# ADCs.net
KiCad netlist of a schematic drawn in Altium Designer
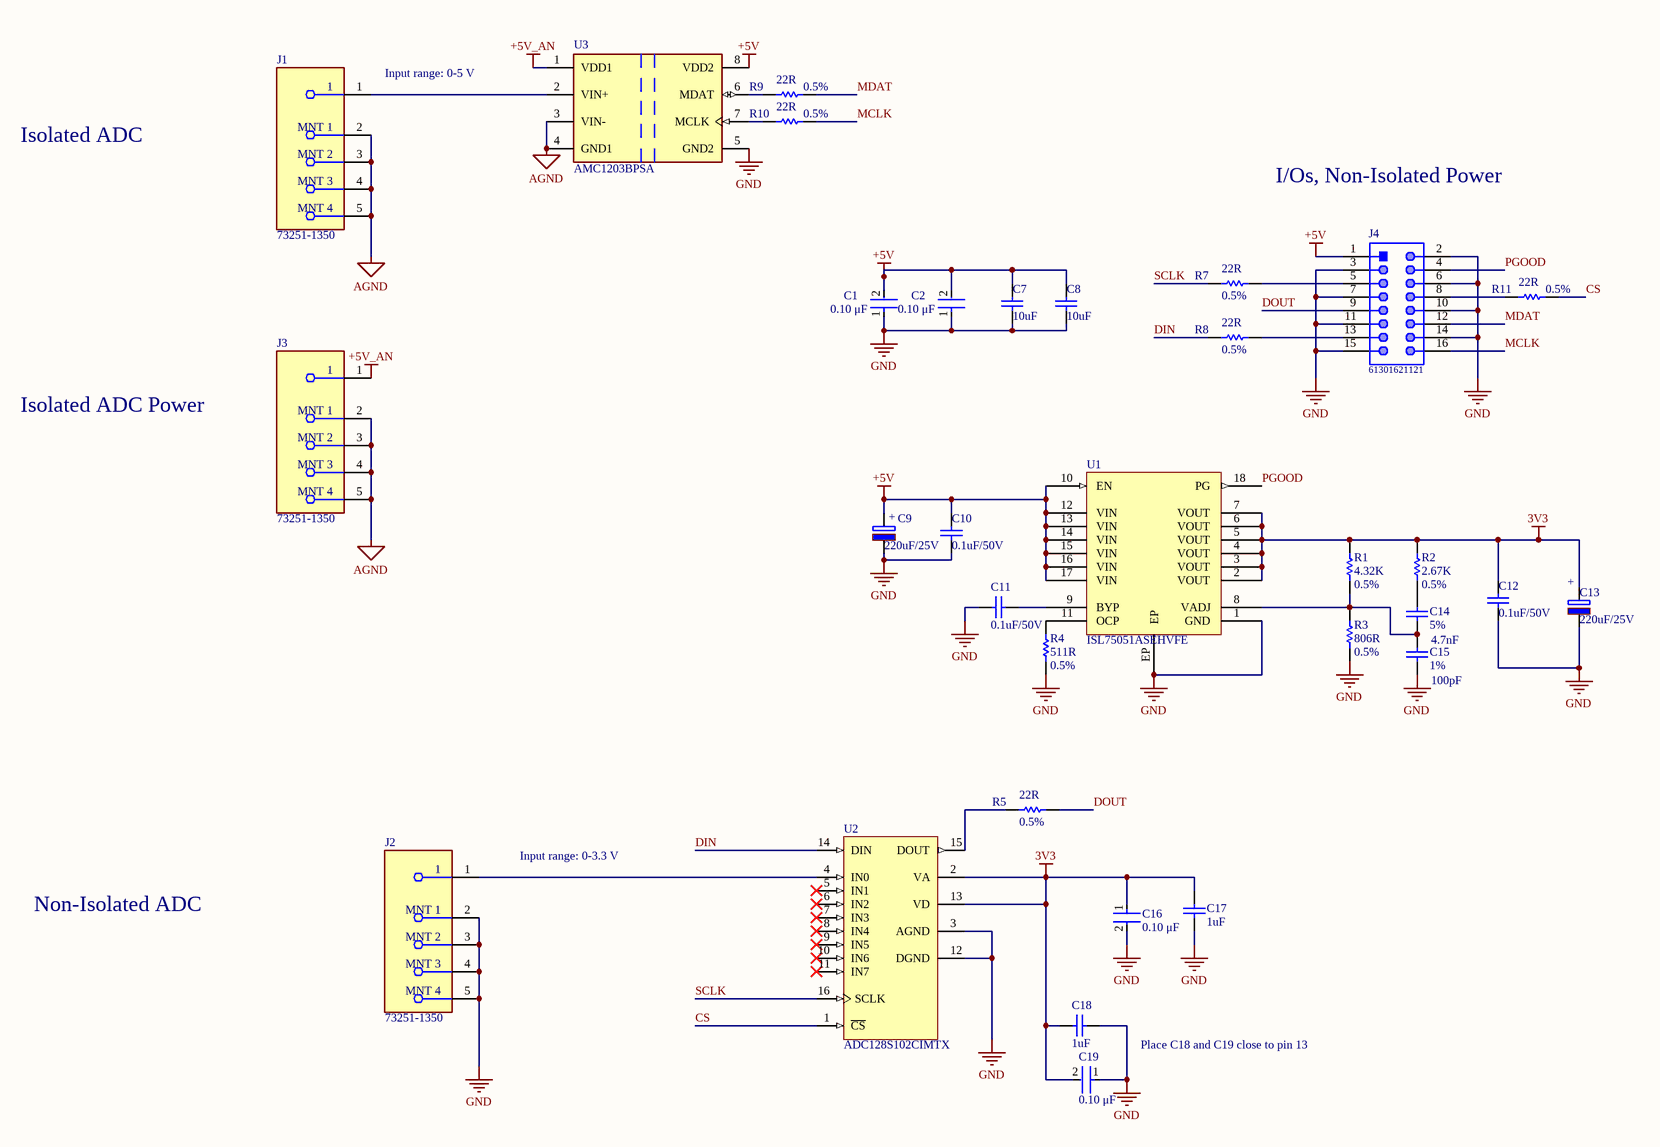
[diagram p0: ADCs.SchDoc]

(export (version "E")
  (design (tool "Eeschema 10.0.6"))
  (components
    (comp (ref "C1")
      (value "0.10 μF")
      (footprint "FP-C0603C-CF-MFG")
      (description "CAP CER 0.1UF 50V 5% X7R 0603")
      (fields (field (name "TOLERANCE") "0.05") (field (name "MANUFACTURER PART NUMBER") "C0603C104J5RACTU"))
      (libsource (lib "Altium Content Vault") (part "b4654b650e69147ec39a6b967a45e02"))
    )
    (comp (ref "C2")
      (value "0.10 μF")
      (footprint "FP-C0603C-CF-MFG")
      (description "CAP CER 0.1UF 50V 5% X7R 0603")
      (fields (field (name "TOLERANCE") "0.05") (field (name "MANUFACTURER PART NUMBER") "C0603C104J5RACTU"))
      (libsource (lib "Altium Content Vault") (part "b4654b650e69147ec39a6b967a45e02"))
    )
    (comp (ref "C7")
      (value "10uF")
      (footprint "CAPC1608X90N")
      (description "CAP CER 10UF 25V X5R 0603")
      (fields
        (field (name "MANUFACTURER PART NUMBER") "GRM188R61E106KA73D")
        (field (name "MANUFACTURER") "Murata Electronics")
      )
      (libsource (lib "Motor Resolver") (part "CAP CER 10UF 25V X5R 0603"))
    )
    (comp (ref "C8")
      (value "10uF")
      (footprint "CAPC1608X90N")
      (description "CAP CER 10UF 25V X5R 0603")
      (fields
        (field (name "MANUFACTURER PART NUMBER") "GRM188R61E106KA73D")
        (field (name "MANUFACTURER") "Murata Electronics")
      )
      (libsource (lib "Motor Resolver") (part "CAP CER 10UF 25V X5R 0603"))
    )
    (comp (ref "C9")
      (value "220uF/25V")
      (footprint "CAP_AE830X1050N")
      (description "CAP ALUM 220UF 20% 25V SMD")
      (fields
        (field (name "MANUFACTURER PART NUMBER") "EMZA250ADA221MHA0G")
        (field (name "MANUFACTURER") "United Chemi-Con")
      )
      (libsource (lib "") (part "CAP ALUM 220UF 20% 25V SMD_1"))
    )
    (comp (ref "C10")
      (value "0.1uF/50V")
      (footprint "CAPC1608X90N")
      (description "CAP CER 0.1UF 50V X7R 0603")
      (fields
        (field (name "MANUFACTURER PART NUMBER") "CL10B104KB8NNNC")
        (field (name "MANUFACTURER") "Samsung Electro-Mechanics")
      )
      (libsource (lib "Motor Resolver") (part "CAP CER 0.1UF 50V X7R 0603"))
    )
    (comp (ref "C11")
      (value "0.1uF/50V")
      (footprint "CAPC1608X90N")
      (description "CAP CER 0.1UF 50V X7R 0603")
      (fields
        (field (name "MANUFACTURER PART NUMBER") "CL10B104KB8NNNC")
        (field (name "MANUFACTURER") "Samsung Electro-Mechanics")
      )
      (libsource (lib "Motor Resolver") (part "CAP CER 0.1UF 50V X7R 0603"))
    )
    (comp (ref "C12")
      (value "0.1uF/50V")
      (footprint "CAPC1608X90N")
      (description "CAP CER 0.1UF 50V X7R 0603")
      (fields
        (field (name "MANUFACTURER PART NUMBER") "CL10B104KB8NNNC")
        (field (name "MANUFACTURER") "Samsung Electro-Mechanics")
      )
      (libsource (lib "Motor Resolver") (part "CAP CER 0.1UF 50V X7R 0603"))
    )
    (comp (ref "C13")
      (value "220uF/25V")
      (footprint "CAP_AE830X1050N")
      (description "CAP ALUM 220UF 20% 25V SMD")
      (fields
        (field (name "MANUFACTURER PART NUMBER") "EMZA250ADA221MHA0G")
        (field (name "MANUFACTURER") "United Chemi-Con")
      )
      (libsource (lib "Motor Resolver") (part "CAP ALUM 220UF 20% 25V SMD"))
    )
    (comp (ref "C14")
      (value "4.7nF")
      (footprint "CAPC1608X90N")
      (description "CAP CER 4700PF 50V C0G 0603")
      (fields
        (field (name "MANUFACTURER PART NUMBER") "CGA3E2C0G1H472J080AA")
        (field (name "MANUFACTURER") "TDK Corporation")
        (field (name "TOLERANCE") "5%")
      )
      (libsource (lib "Motor Resolver") (part "CAP CER 4700PF 50V C0G 0603"))
    )
    (comp (ref "C15")
      (value "100pF")
      (footprint "CAPC1608X90N")
      (description "CAP CER 100PF 50V C0G/NP0 0603")
      (fields
        (field (name "MANUFACTURER PART NUMBER") "06035A101FAT2A")
        (field (name "MANUFACTURER") "KYOCERA AVX")
        (field (name "TOLERANCE") "1%")
      )
      (libsource (lib "Motor Resolver") (part "CAP CER 100PF 50V C0G/NP0 0603"))
    )
    (comp (ref "C16")
      (value "0.10 μF")
      (footprint "FP-C0603C-CF-MFG")
      (description "CAP CER 0.1UF 50V 5% X7R 0603")
      (fields (field (name "TOLERANCE") "0.05") (field (name "MANUFACTURER PART NUMBER") "C0603C104J5RACTU"))
      (libsource (lib "Altium Content Vault") (part "b4654b650e69147ec39a6b967a45e02"))
    )
    (comp (ref "C17")
      (value "1uF")
      (footprint "CAPC1608X90N")
      (description "CAP CER 1UF 25V X7R 0603")
      (fields
        (field (name "MANUFACTURER PART NUMBER") "GCM188R71E105KA64D")
        (field (name "MANUFACTURER") "Murata Electronics")
      )
      (libsource (lib "Motor Resolver") (part "CAP CER 1UF 25V X7R 0603"))
    )
    (comp (ref "C18")
      (value "1uF")
      (footprint "CAPC1608X90N")
      (description "CAP CER 1UF 25V X7R 0603")
      (fields
        (field (name "MANUFACTURER PART NUMBER") "GCM188R71E105KA64D")
        (field (name "MANUFACTURER") "Murata Electronics")
      )
      (libsource (lib "Motor Resolver") (part "CAP CER 1UF 25V X7R 0603"))
    )
    (comp (ref "C19")
      (value "0.10 μF")
      (footprint "FP-C0603C-CF-MFG")
      (description "CAP CER 0.1UF 50V 5% X7R 0603")
      (fields (field (name "TOLERANCE") "0.05") (field (name "MANUFACTURER PART NUMBER") "C0603C104J5RACTU"))
      (libsource (lib "Altium Content Vault") (part "b4654b650e69147ec39a6b967a45e02"))
    )
    (comp (ref "J1")
      (value "73251-1350")
      (footprint "FP-73251-1350-MFG")
      (description "CONN SMA JACK STR 50 OHM SMD")
      (fields
        (field (name "OCTOPART") "https://octopart.com/73251-1350-molex-5414390")
        (field (name "MANUFACTURER") "Molex")
      )
      (libsource (lib "Altium Content Vault") (part "474d33b8a96b1ade9ed6dd87a2b06d4"))
    )
    (comp (ref "J2")
      (value "73251-1350")
      (footprint "FP-73251-1350-MFG")
      (description "CONN SMA JACK STR 50 OHM SMD")
      (fields
        (field (name "OCTOPART") "https://octopart.com/73251-1350-molex-5414390")
        (field (name "MANUFACTURER") "Molex")
      )
      (libsource (lib "Altium Content Vault") (part "474d33b8a96b1ade9ed6dd87a2b06d4"))
    )
    (comp (ref "J3")
      (value "73251-1350")
      (footprint "FP-73251-1350-MFG")
      (description "CONN SMA JACK STR 50 OHM SMD")
      (fields
        (field (name "OCTOPART") "https://octopart.com/73251-1350-molex-5414390")
        (field (name "MANUFACTURER") "Molex")
      )
      (libsource (lib "Altium Content Vault") (part "474d33b8a96b1ade9ed6dd87a2b06d4"))
    )
    (comp (ref "J4")
      (value "61301621121")
      (footprint "61301621121")
      (description "THT Vertical Pin Header WR-PHD, Pitch 2.54 mm, Dual Row, 16 pins")
      (fields (field (name "MANUFACTURER") "Wurth Elektronik") (field (name "PUBLISHER") "WurthElektronik"))
      (libsource (lib "Altium Content Vault") (part "WE-CN-2P-M-R16"))
    )
    (comp (ref "R1")
      (value "4.32K")
      (footprint "RESC1608X55N")
      (description "RES SMD 4.32K OHM 0.5% 1/5W 0603")
      (fields
        (field (name "MANUFACTURER") "Panasonic Electronic Components")
        (field (name "MANUFACTURER PART NUMBER") "ERJ-PB3D4321V")
        (field (name "TOLERANCE") "0.5%")
      )
      (libsource (lib "Motor Resolver") (part "RES SMD 4.32K OHM 0.5% 1/5W 0603"))
    )
    (comp (ref "R2")
      (value "2.67K")
      (footprint "RESC1608X55N")
      (description "RES SMD 2.67KOHM 0.5% 1/10W 0603")
      (fields
        (field (name "MANUFACTURER") "Yageo")
        (field (name "MANUFACTURER PART NUMBER") "RT0603DRD072K67L")
        (field (name "TOLERANCE") "0.5%")
      )
      (libsource (lib "Motor Resolver") (part "RES SMD 2.67KOHM 0.5% 1/10W 0603"))
    )
    (comp (ref "R3")
      (value "806R")
      (footprint "RESC1608X55N")
      (description "RES SMD 806 OHM 0.5% 1/10W 0603")
      (fields
        (field (name "MANUFACTURER") "Yageo")
        (field (name "MANUFACTURER PART NUMBER") "RT0603DRD0762KL")
        (field (name "TOLERANCE") "0.5%")
      )
      (libsource (lib "Motor Resolver") (part "RES SMD 806 OHM 0.5% 1/10W 0603"))
    )
    (comp (ref "R4")
      (value "511R")
      (footprint "RESC1608X55N")
      (description "RES SMD 511 OHM 1% 1/10W 0603")
      (fields
        (field (name "MANUFACTURER") "Panasonic Electronic Components")
        (field (name "MANUFACTURER PART NUMBER") "ERJ-3EKF5110V")
        (field (name "TOLERANCE") "0.5%")
      )
      (libsource (lib "Motor Resolver") (part "RES SMD 511 OHM 1% 1/10W 0603"))
    )
    (comp (ref "R5")
      (value "22R")
      (footprint "RESC1608X55N")
      (description "RES SMD 22 OHM 0.5% 1/10W 0603")
      (fields
        (field (name "MANUFACTURER") "Yageo")
        (field (name "MANUFACTURER PART NUMBER") "RT0603DRD0722RL")
        (field (name "TOLERANCE") "0.5%")
      )
      (libsource (lib "Motor Resolver") (part "RES SMD 22 OHM 0.5% 1/10W 0603"))
    )
    (comp (ref "R7")
      (value "22R")
      (footprint "RESC1608X55N")
      (description "RES SMD 22 OHM 0.5% 1/10W 0603")
      (fields
        (field (name "MANUFACTURER") "Yageo")
        (field (name "MANUFACTURER PART NUMBER") "RT0603DRD0722RL")
        (field (name "TOLERANCE") "0.5%")
      )
      (libsource (lib "Motor Resolver") (part "RES SMD 22 OHM 0.5% 1/10W 0603"))
    )
    (comp (ref "R8")
      (value "22R")
      (footprint "RESC1608X55N")
      (description "RES SMD 22 OHM 0.5% 1/10W 0603")
      (fields
        (field (name "MANUFACTURER") "Yageo")
        (field (name "MANUFACTURER PART NUMBER") "RT0603DRD0722RL")
        (field (name "TOLERANCE") "0.5%")
      )
      (libsource (lib "Motor Resolver") (part "RES SMD 22 OHM 0.5% 1/10W 0603"))
    )
    (comp (ref "R9")
      (value "22R")
      (footprint "RESC1608X55N")
      (description "RES SMD 22 OHM 0.5% 1/10W 0603")
      (fields
        (field (name "MANUFACTURER") "Yageo")
        (field (name "MANUFACTURER PART NUMBER") "RT0603DRD0722RL")
        (field (name "TOLERANCE") "0.5%")
      )
      (libsource (lib "Motor Resolver") (part "RES SMD 22 OHM 0.5% 1/10W 0603"))
    )
    (comp (ref "R10")
      (value "22R")
      (footprint "RESC1608X55N")
      (description "RES SMD 22 OHM 0.5% 1/10W 0603")
      (fields
        (field (name "MANUFACTURER") "Yageo")
        (field (name "MANUFACTURER PART NUMBER") "RT0603DRD0722RL")
        (field (name "TOLERANCE") "0.5%")
      )
      (libsource (lib "Motor Resolver") (part "RES SMD 22 OHM 0.5% 1/10W 0603"))
    )
    (comp (ref "R11")
      (value "22R")
      (footprint "RESC1608X55N")
      (description "RES SMD 22 OHM 0.5% 1/10W 0603")
      (fields
        (field (name "MANUFACTURER") "Yageo")
        (field (name "MANUFACTURER PART NUMBER") "RT0603DRD0722RL")
        (field (name "TOLERANCE") "0.5%")
      )
      (libsource (lib "Motor Resolver") (part "RES SMD 22 OHM 0.5% 1/10W 0603"))
    )
    (comp (ref "U1")
      (value "ISL75051ASEHVFE")
      (footprint "CFP102P1520X310-18AN")
      (description "Voltage regulator, linear, variable, 3 A, CFP-18 exposed pad, class V")
      (fields
        (field (name "MANUFACTURER") "Renesas / Intersil")
        (field (name "FM (SMD) PART NUMBER") "5962R1121203VYC")
      )
      (libsource (lib "Motor Resolver") (part "ISL75051ASEHVFE"))
    )
    (comp (ref "U2")
      (value "ADC128S102CIMTX")
      (footprint "MTC16_N")
      (description "8-Channel, 500 kSPS to 1 MSPS, 12-Bit A/D Converter, 16-pin TSSOP")
      (fields (field (name "MANUFACTURER") "National Semiconductor"))
      (libsource (lib "Altium Content Vault") (part "CON-ADC-ADC108S052CIMT"))
    )
    (comp (ref "U3")
      (value "AMC1203BPSA")
      (footprint "FP-PSA0008A-IPC_C")
      (description "IC ADC 16BIT SIGMA-DELTA 8SOP")
      (libsource (lib "Altium Content Vault") (part "402472702e68974f8122a6dcee3cdea"))
    )
  )
  (nets
    (net (code "1") (name "+5V") (class "Default")
      (node (ref "C1") (pin "2") (pinfunction "2_2") (pintype "passive"))
      (node (ref "C10") (pin "1") (pinfunction "1_1") (pintype "passive"))
      (node (ref "C2") (pin "2") (pinfunction "2_2") (pintype "passive"))
      (node (ref "C7") (pin "1") (pinfunction "1_1") (pintype "passive"))
      (node (ref "C8") (pin "1") (pinfunction "1_1") (pintype "passive"))
      (node (ref "C9") (pin "1") (pinfunction "1_1") (pintype "passive"))
      (node (ref "J4") (pin "1") (pinfunction "1_1") (pintype "passive"))
      (node (ref "U1") (pin "10") (pinfunction "EN_10") (pintype "input"))
      (node (ref "U1") (pin "12") (pinfunction "VIN_12") (pintype "power_in"))
      (node (ref "U1") (pin "13") (pinfunction "VIN_13") (pintype "power_in"))
      (node (ref "U1") (pin "14") (pinfunction "VIN_14") (pintype "power_in"))
      (node (ref "U1") (pin "15") (pinfunction "VIN_15") (pintype "power_in"))
      (node (ref "U1") (pin "16") (pinfunction "VIN_16") (pintype "power_in"))
      (node (ref "U1") (pin "17") (pinfunction "VIN_17") (pintype "power_in"))
      (node (ref "U3") (pin "8") (pinfunction "VDD2_8") (pintype "power_in"))
    )
    (net (code "2") (name "+5V_AN") (class "Default")
      (node (ref "J3") (pin "1") (pinfunction "1_1") (pintype "passive"))
      (node (ref "U3") (pin "1") (pinfunction "VDD1_1") (pintype "power_in"))
    )
    (net (code "3") (name "/CS") (class "Default")
      (node (ref "R11") (pin "2") (pinfunction "2_2") (pintype "passive"))
      (node (ref "U2") (pin "1") (pinfunction "~{CS}_1") (pintype "input"))
    )
    (net (code "4") (name "/DIN") (class "Default")
      (node (ref "R8") (pin "1") (pinfunction "1_1") (pintype "passive"))
      (node (ref "U2") (pin "14") (pinfunction "DIN_14") (pintype "input"))
    )
    (net (code "5") (name "/DOUT") (class "Default")
      (node (ref "J4") (pin "9") (pinfunction "9_9") (pintype "passive"))
      (node (ref "R5") (pin "2") (pinfunction "2_2") (pintype "passive"))
    )
    (net (code "6") (name "/MCLK") (class "Default")
      (node (ref "J4") (pin "16") (pinfunction "16_16") (pintype "passive"))
      (node (ref "R10") (pin "2") (pinfunction "2_2") (pintype "passive"))
    )
    (net (code "7") (name "/MDAT") (class "Default")
      (node (ref "J4") (pin "12") (pinfunction "12_12") (pintype "passive"))
      (node (ref "R9") (pin "2") (pinfunction "2_2") (pintype "passive"))
    )
    (net (code "8") (name "/PGOOD") (class "Default")
      (node (ref "J4") (pin "4") (pinfunction "4_4") (pintype "passive"))
      (node (ref "U1") (pin "18") (pinfunction "PG_18") (pintype "output"))
    )
    (net (code "9") (name "/SCLK") (class "Default")
      (node (ref "R7") (pin "1") (pinfunction "1_1") (pintype "passive"))
      (node (ref "U2") (pin "16") (pinfunction "SCLK_16") (pintype "input"))
    )
    (net (code "10") (name "3V3") (class "Default")
      (node (ref "C12") (pin "1") (pinfunction "1_1") (pintype "passive"))
      (node (ref "C13") (pin "1") (pinfunction "1_1") (pintype "passive"))
      (node (ref "C16") (pin "1") (pinfunction "1_1") (pintype "passive"))
      (node (ref "C17") (pin "1") (pinfunction "1_1") (pintype "passive"))
      (node (ref "C18") (pin "2") (pinfunction "2_2") (pintype "passive"))
      (node (ref "C19") (pin "2") (pinfunction "2_2") (pintype "passive"))
      (node (ref "R1") (pin "2") (pinfunction "2_2") (pintype "passive"))
      (node (ref "R2") (pin "2") (pinfunction "2_2") (pintype "passive"))
      (node (ref "U1") (pin "2") (pinfunction "VOUT_2") (pintype "power_in"))
      (node (ref "U1") (pin "3") (pinfunction "VOUT_3") (pintype "power_in"))
      (node (ref "U1") (pin "4") (pinfunction "VOUT_4") (pintype "power_in"))
      (node (ref "U1") (pin "5") (pinfunction "VOUT_5") (pintype "power_in"))
      (node (ref "U1") (pin "6") (pinfunction "VOUT_6") (pintype "power_in"))
      (node (ref "U1") (pin "7") (pinfunction "VOUT_7") (pintype "power_in"))
      (node (ref "U2") (pin "13") (pinfunction "VD_13") (pintype "power_in"))
      (node (ref "U2") (pin "2") (pinfunction "VA_2") (pintype "power_in"))
    )
    (net (code "11") (name "AGND") (class "Default")
      (node (ref "J1") (pin "2") (pinfunction "MNT_1_2") (pintype "passive"))
      (node (ref "J1") (pin "3") (pinfunction "MNT_2_3") (pintype "passive"))
      (node (ref "J1") (pin "4") (pinfunction "MNT_3_4") (pintype "passive"))
      (node (ref "J1") (pin "5") (pinfunction "MNT_4_5") (pintype "passive"))
      (node (ref "J3") (pin "2") (pinfunction "MNT_1_2") (pintype "passive"))
      (node (ref "J3") (pin "3") (pinfunction "MNT_2_3") (pintype "passive"))
      (node (ref "J3") (pin "4") (pinfunction "MNT_3_4") (pintype "passive"))
      (node (ref "J3") (pin "5") (pinfunction "MNT_4_5") (pintype "passive"))
      (node (ref "U3") (pin "3") (pinfunction "VIN-_3") (pintype "tri_state"))
      (node (ref "U3") (pin "4") (pinfunction "GND1_4") (pintype "power_in"))
    )
    (net (code "12") (name "GND") (class "Default")
      (node (ref "C1") (pin "1") (pinfunction "1_1") (pintype "passive"))
      (node (ref "C10") (pin "2") (pinfunction "2_2") (pintype "passive"))
      (node (ref "C11") (pin "2") (pinfunction "2_2") (pintype "passive"))
      (node (ref "C12") (pin "2") (pinfunction "2_2") (pintype "passive"))
      (node (ref "C13") (pin "2") (pinfunction "2_2") (pintype "passive"))
      (node (ref "C15") (pin "2") (pinfunction "2_2") (pintype "passive"))
      (node (ref "C16") (pin "2") (pinfunction "2_2") (pintype "passive"))
      (node (ref "C17") (pin "2") (pinfunction "2_2") (pintype "passive"))
      (node (ref "C18") (pin "1") (pinfunction "1_1") (pintype "passive"))
      (node (ref "C19") (pin "1") (pinfunction "1_1") (pintype "passive"))
      (node (ref "C2") (pin "1") (pinfunction "1_1") (pintype "passive"))
      (node (ref "C7") (pin "2") (pinfunction "2_2") (pintype "passive"))
      (node (ref "C8") (pin "2") (pinfunction "2_2") (pintype "passive"))
      (node (ref "C9") (pin "2") (pinfunction "2_2") (pintype "passive"))
      (node (ref "J2") (pin "2") (pinfunction "MNT_1_2") (pintype "passive"))
      (node (ref "J2") (pin "3") (pinfunction "MNT_2_3") (pintype "passive"))
      (node (ref "J2") (pin "4") (pinfunction "MNT_3_4") (pintype "passive"))
      (node (ref "J2") (pin "5") (pinfunction "MNT_4_5") (pintype "passive"))
      (node (ref "J4") (pin "10") (pinfunction "10_10") (pintype "passive"))
      (node (ref "J4") (pin "11") (pinfunction "11_11") (pintype "passive"))
      (node (ref "J4") (pin "14") (pinfunction "14_14") (pintype "passive"))
      (node (ref "J4") (pin "15") (pinfunction "15_15") (pintype "passive"))
      (node (ref "J4") (pin "2") (pinfunction "2_2") (pintype "passive"))
      (node (ref "J4") (pin "3") (pinfunction "3_3") (pintype "passive"))
      (node (ref "J4") (pin "6") (pinfunction "6_6") (pintype "passive"))
      (node (ref "J4") (pin "7") (pinfunction "7_7") (pintype "passive"))
      (node (ref "R3") (pin "1") (pinfunction "1_1") (pintype "passive"))
      (node (ref "R4") (pin "1") (pinfunction "1_1") (pintype "passive"))
      (node (ref "U1") (pin "1") (pinfunction "GND_1") (pintype "power_in"))
      (node (ref "U1") (pin "EP") (pinfunction "EP_EP") (pintype "passive"))
      (node (ref "U2") (pin "12") (pinfunction "DGND_12") (pintype "power_in"))
      (node (ref "U2") (pin "3") (pinfunction "AGND_3") (pintype "power_in"))
      (node (ref "U3") (pin "5") (pinfunction "GND2_5") (pintype "power_in"))
    )
    (net (code "13") (name "Net-(C14-Pad1)") (class "Default")
      (node (ref "C14") (pin "1") (pinfunction "1_1") (pintype "passive"))
      (node (ref "R2") (pin "1") (pinfunction "1_1") (pintype "passive"))
    )
    (net (code "14") (name "Net-(J4-Pad5)") (class "Default")
      (node (ref "J4") (pin "5") (pinfunction "5_5") (pintype "passive"))
      (node (ref "R7") (pin "2") (pinfunction "2_2") (pintype "passive"))
    )
    (net (code "15") (name "Net-(J4-Pad8)") (class "Default")
      (node (ref "J4") (pin "8") (pinfunction "8_8") (pintype "passive"))
      (node (ref "R11") (pin "1") (pinfunction "1_1") (pintype "passive"))
    )
    (net (code "16") (name "Net-(J4-Pad13)") (class "Default")
      (node (ref "J4") (pin "13") (pinfunction "13_13") (pintype "passive"))
      (node (ref "R8") (pin "2") (pinfunction "2_2") (pintype "passive"))
    )
    (net (code "17") (name "Net-(U1-BYP)") (class "Default")
      (node (ref "C11") (pin "1") (pinfunction "1_1") (pintype "passive"))
      (node (ref "U1") (pin "9") (pinfunction "BYP_9") (pintype "passive"))
    )
    (net (code "18") (name "Net-(U1-OCP)") (class "Default")
      (node (ref "R4") (pin "2") (pinfunction "2_2") (pintype "passive"))
      (node (ref "U1") (pin "11") (pinfunction "OCP_11") (pintype "passive"))
    )
    (net (code "19") (name "Net-(U1-VADJ)") (class "Default")
      (node (ref "C14") (pin "2") (pinfunction "2_2") (pintype "passive"))
      (node (ref "C15") (pin "1") (pinfunction "1_1") (pintype "passive"))
      (node (ref "R1") (pin "1") (pinfunction "1_1") (pintype "passive"))
      (node (ref "R3") (pin "2") (pinfunction "2_2") (pintype "passive"))
      (node (ref "U1") (pin "8") (pinfunction "VADJ_8") (pintype "passive"))
    )
    (net (code "20") (name "Net-(U2-DOUT)") (class "Default")
      (node (ref "R5") (pin "1") (pinfunction "1_1") (pintype "passive"))
      (node (ref "U2") (pin "15") (pinfunction "DOUT_15") (pintype "output"))
    )
    (net (code "21") (name "Net-(U2-IN0)") (class "Default")
      (node (ref "J2") (pin "1") (pinfunction "1_1") (pintype "passive"))
      (node (ref "U2") (pin "4") (pinfunction "IN0_4") (pintype "input"))
    )
    (net (code "22") (name "Net-(U3-MCLK)") (class "Default")
      (node (ref "R10") (pin "1") (pinfunction "1_1") (pintype "passive"))
      (node (ref "U3") (pin "7") (pinfunction "MCLK_7") (pintype "input"))
    )
    (net (code "23") (name "Net-(U3-MDAT)") (class "Default")
      (node (ref "R9") (pin "1") (pinfunction "1_1") (pintype "passive"))
      (node (ref "U3") (pin "6") (pinfunction "MDAT_6") (pintype "bidirectional"))
    )
    (net (code "24") (name "Net-(U3-VIN+)") (class "Default")
      (node (ref "J1") (pin "1") (pinfunction "1_1") (pintype "passive"))
      (node (ref "U3") (pin "2") (pinfunction "VIN+_2") (pintype "tri_state"))
    )
    (net (code "25") (name "unconnected-(U2-IN1-Pad5)") (class "Default")
      (node (ref "U2") (pin "5") (pinfunction "IN1_5") (pintype "input+no_connect"))
    )
    (net (code "26") (name "unconnected-(U2-IN2-Pad6)") (class "Default")
      (node (ref "U2") (pin "6") (pinfunction "IN2_6") (pintype "input+no_connect"))
    )
    (net (code "27") (name "unconnected-(U2-IN3-Pad7)") (class "Default")
      (node (ref "U2") (pin "7") (pinfunction "IN3_7") (pintype "input+no_connect"))
    )
    (net (code "28") (name "unconnected-(U2-IN4-Pad8)") (class "Default")
      (node (ref "U2") (pin "8") (pinfunction "IN4_8") (pintype "input+no_connect"))
    )
    (net (code "29") (name "unconnected-(U2-IN5-Pad9)") (class "Default")
      (node (ref "U2") (pin "9") (pinfunction "IN5_9") (pintype "input+no_connect"))
    )
    (net (code "30") (name "unconnected-(U2-IN6-Pad10)") (class "Default")
      (node (ref "U2") (pin "10") (pinfunction "IN6_10") (pintype "input+no_connect"))
    )
    (net (code "31") (name "unconnected-(U2-IN7-Pad11)") (class "Default")
      (node (ref "U2") (pin "11") (pinfunction "IN7_11") (pintype "input+no_connect"))
    )
  )
)
